# current_sensor_power.net
KiCad netlist of a schematic drawn in Altium Designer
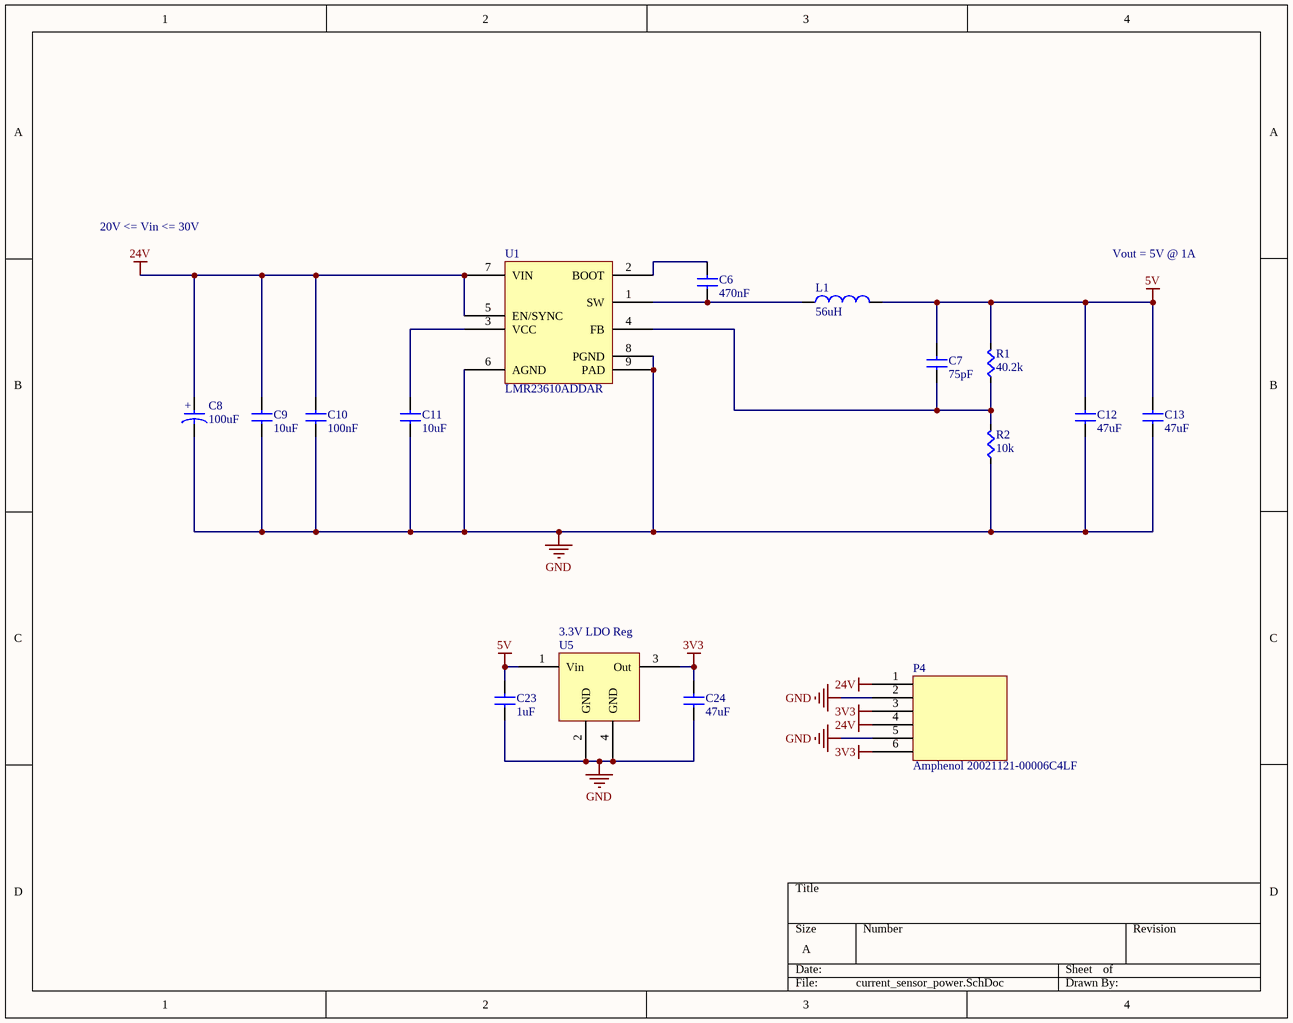
[diagram p0: current_sensor_power.SchDoc]

(export (version "E")
  (design (tool "Eeschema 10.0.6"))
  (components
    (comp (ref "C6")
      (value "470nF")
      (footprint "CAPC0603")
      (fields (field (name "Comment") "Cap"))
      (libsource (lib "Passives") (part "Cap"))
    )
    (comp (ref "C7")
      (value "75pF")
      (footprint "CAPC0603")
      (fields (field (name "Comment") "Cap"))
      (libsource (lib "Passives") (part "Cap"))
    )
    (comp (ref "C8")
      (value "100uF")
      (footprint "EEHZA1H101P")
      (description "CAP ALUM POLY HYB 100UF 50V SMD")
      (fields (field (name "VOLTAGE") "50V") (field (name "TOLERANCE") "20%"))
      (libsource (lib "SubjuGator8") (part "EEHZA1H101P"))
    )
    (comp (ref "C9")
      (value "10uF")
      (footprint "CAP1210")
      (fields (field (name "Comment") "Cap"))
      (libsource (lib "Passives") (part "Cap"))
    )
    (comp (ref "C10")
      (value "100nF")
      (footprint "CAPC0603")
      (fields (field (name "Comment") "Cap"))
      (libsource (lib "Passives") (part "Cap"))
    )
    (comp (ref "C11")
      (value "10uF")
      (footprint "CAPC0603")
      (fields (field (name "Comment") "Cap"))
      (libsource (lib "Passives") (part "Cap"))
    )
    (comp (ref "C12")
      (value "47uF")
      (footprint "CAP1210")
      (fields (field (name "Comment") "Cap"))
      (libsource (lib "SubjuGator8") (part "Cap"))
    )
    (comp (ref "C13")
      (value "47uF")
      (footprint "CAP1210")
      (fields (field (name "Comment") "Cap"))
      (libsource (lib "SubjuGator8") (part "Cap"))
    )
    (comp (ref "C23")
      (value "1uF")
      (footprint "CAPC0603")
      (fields (field (name "MANUFACTURER PART NUMBER") "C0603C105K8PACTU") (field (name "Comment") "Cap"))
      (libsource (lib "SubjuGator8") (part "Cap"))
    )
    (comp (ref "C24")
      (value "47uF")
      (footprint "CAPC0603")
      (fields (field (name "MANUFACTURER PART NUMBER") "C0603C105K8PACTU") (field (name "Comment") "Cap"))
      (libsource (lib "SubjuGator8") (part "Cap"))
    )
    (comp (ref "L1")
      (value "56uH")
      (footprint "MSS1048-563MLB")
      (description "FIXED IND 56UH 1.7A 126 MOHM")
      (fields (field (name "Comment") "MSS1048-563MLB"))
      (libsource (lib "SubjuGator8") (part "MSS1048-563MLB"))
    )
    (comp (ref "P4")
      (value "Amphenol 20021121-00006C4LF")
      (footprint "Amphenol FCI 20021121-00006C4LF")
      (description "6 Positions Header Connector 0.050\" (1.27mm) Surface Mount Gold")
      (libsource (lib "SubjuGator8") (part "Amphenol FCI 20021121-00006C4LF"))
    )
    (comp (ref "R1")
      (value "40.2k")
      (footprint "RES0603")
      (fields (field (name "Comment") "Res"))
      (libsource (lib "SubjuGator8") (part "Res"))
    )
    (comp (ref "R2")
      (value "10k")
      (footprint "RES0603")
      (fields (field (name "Comment") "Res"))
      (libsource (lib "SubjuGator8") (part "Res"))
    )
    (comp (ref "U1")
      (value "LMR23610ADDAR")
      (footprint "LMR23610ADDAR")
      (description "IC REG BUCK ADJ 1A SYNC 8SOPWRPD")
      (libsource (lib "SubjuGator8") (part "LMR23610ADDAR"))
    )
    (comp (ref "U5")
      (value "3.3V LDO Reg")
      (footprint "SOT23-4n")
      (description "IC REG LDO 3.3V 1A SOT223")
      (libsource (lib "SubjuGator8") (part "LM3940IMPX-3.3"))
    )
  )
  (nets
    (net (code "1") (name "3V3") (class "Default")
      (node (ref "C24") (pin "1") (pinfunction "A_1") (pintype "passive"))
      (node (ref "P4") (pin "3") (pintype "passive"))
      (node (ref "P4") (pin "6") (pintype "passive"))
      (node (ref "U5") (pin "3") (pinfunction "Out_3") (pintype "passive"))
    )
    (net (code "2") (name "5V") (class "Default")
      (node (ref "C12") (pin "1") (pinfunction "A_1") (pintype "passive"))
      (node (ref "C13") (pin "1") (pinfunction "A_1") (pintype "passive"))
      (node (ref "C23") (pin "1") (pinfunction "A_1") (pintype "passive"))
      (node (ref "C7") (pin "1") (pinfunction "A_1") (pintype "passive"))
      (node (ref "L1") (pin "2") (pinfunction "2_2") (pintype "passive"))
      (node (ref "R1") (pin "1") (pinfunction "A_1") (pintype "passive"))
      (node (ref "U5") (pin "1") (pinfunction "Vin_1") (pintype "passive"))
    )
    (net (code "3") (name "24V") (class "Default")
      (node (ref "C10") (pin "1") (pinfunction "A_1") (pintype "passive"))
      (node (ref "C8") (pin "1") (pinfunction "1_1") (pintype "passive"))
      (node (ref "C9") (pin "1") (pinfunction "A_1") (pintype "passive"))
      (node (ref "P4") (pin "1") (pintype "passive"))
      (node (ref "P4") (pin "4") (pintype "passive"))
      (node (ref "U1") (pin "5") (pinfunction "EN/SYNC_5") (pintype "passive"))
      (node (ref "U1") (pin "7") (pinfunction "VIN_7") (pintype "passive"))
    )
    (net (code "4") (name "GND") (class "Default")
      (node (ref "C10") (pin "2") (pinfunction "B_2") (pintype "passive"))
      (node (ref "C11") (pin "2") (pinfunction "B_2") (pintype "passive"))
      (node (ref "C12") (pin "2") (pinfunction "B_2") (pintype "passive"))
      (node (ref "C13") (pin "2") (pinfunction "B_2") (pintype "passive"))
      (node (ref "C23") (pin "2") (pinfunction "B_2") (pintype "passive"))
      (node (ref "C24") (pin "2") (pinfunction "B_2") (pintype "passive"))
      (node (ref "C8") (pin "2") (pinfunction "2_2") (pintype "passive"))
      (node (ref "C9") (pin "2") (pinfunction "B_2") (pintype "passive"))
      (node (ref "P4") (pin "2") (pintype "passive"))
      (node (ref "P4") (pin "5") (pintype "passive"))
      (node (ref "R2") (pin "2") (pinfunction "B_2") (pintype "passive"))
      (node (ref "U1") (pin "6") (pinfunction "AGND_6") (pintype "passive"))
      (node (ref "U1") (pin "8") (pinfunction "PGND_8") (pintype "passive"))
      (node (ref "U1") (pin "9") (pinfunction "PAD_9") (pintype "passive"))
      (node (ref "U5") (pin "2") (pinfunction "GND_2") (pintype "passive"))
      (node (ref "U5") (pin "4") (pinfunction "GND_4") (pintype "passive"))
    )
    (net (code "5") (name "Net-(C6-A)") (class "Default")
      (node (ref "C6") (pin "1") (pinfunction "A_1") (pintype "passive"))
      (node (ref "U1") (pin "2") (pinfunction "BOOT_2") (pintype "passive"))
    )
    (net (code "6") (name "Net-(C6-B)") (class "Default")
      (node (ref "C6") (pin "2") (pinfunction "B_2") (pintype "passive"))
      (node (ref "L1") (pin "1") (pinfunction "1_1") (pintype "passive"))
      (node (ref "U1") (pin "1") (pinfunction "SW_1") (pintype "passive"))
    )
    (net (code "7") (name "Net-(C7-B)") (class "Default")
      (node (ref "C7") (pin "2") (pinfunction "B_2") (pintype "passive"))
      (node (ref "R1") (pin "2") (pinfunction "B_2") (pintype "passive"))
      (node (ref "R2") (pin "1") (pinfunction "A_1") (pintype "passive"))
      (node (ref "U1") (pin "4") (pinfunction "FB_4") (pintype "passive"))
    )
    (net (code "8") (name "Net-(C11-A)") (class "Default")
      (node (ref "C11") (pin "1") (pinfunction "A_1") (pintype "passive"))
      (node (ref "U1") (pin "3") (pinfunction "VCC_3") (pintype "passive"))
    )
  )
)
